# heating_pad_5v_to_3v.net
KiCad netlist of a schematic drawn in EAGLE
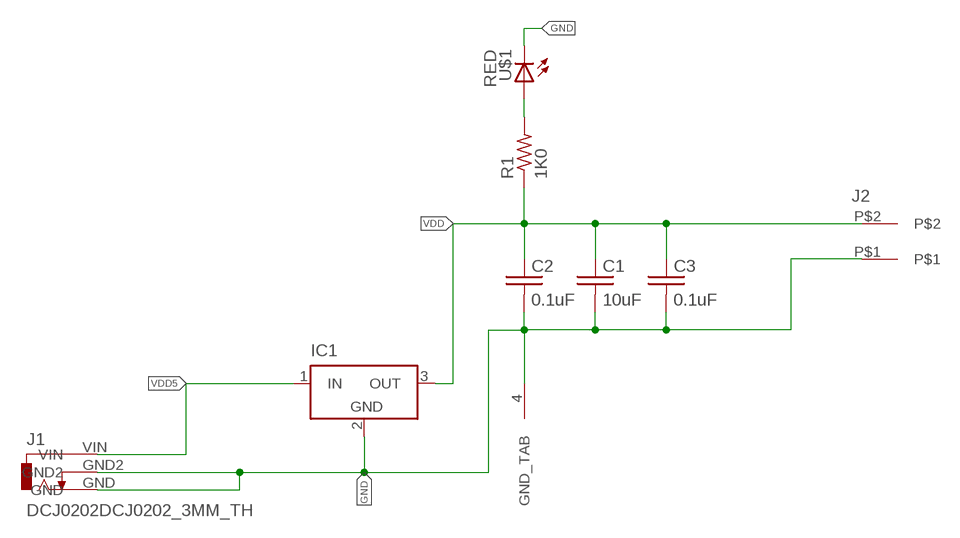
[diagram p0: schematic, sheet 1]

(export (version "E")
  (design (tool "Eeschema 10.0.6"))
  (components
    (comp (ref "C1")
      (value "10uF")
      (footprint "eagle-import:0402")
      (fields (field (name "PARTNO") "CL05A106MP8NUB8"))
      (libsource (lib "eagle-import") (part "C_0402_10UF"))
    )
    (comp (ref "C2")
      (value "0.1uF")
      (footprint "eagle-import:0402")
      (fields (field (name "PARTNO") "CL05F104ZO5NNNC"))
      (libsource (lib "eagle-import") (part "C_0402_0.1UF"))
    )
    (comp (ref "C3")
      (value "0.1uF")
      (footprint "eagle-import:0402")
      (fields (field (name "PARTNO") "CL05F104ZO5NNNC"))
      (libsource (lib "eagle-import") (part "C_0402_0.1UF"))
    )
    (comp (ref "IC1")
      (value "LT1129CST3")
      (footprint "eagle-import:SOT223")
      (libsource (lib "eagle-import") (part "LT1129CST3"))
    )
    (comp (ref "J1")
      (value "DCJ0202DCJ0202_3MM_TH")
      (footprint "eagle-import:DCJ0202_3MM_TH")
      (libsource (lib "eagle-import") (part "DCJ0202DCJ0202_3MM_TH"))
    )
    (comp (ref "J2")
      (value "2-pos")
      (footprint "eagle-import:2_3.81MM_PITCH")
      (fields (field (name "PARTNO") "691322310002"))
      (libsource (lib "eagle-import") (part "3.81MM_1_X_2_RT_ANGLE_PLUG_HEADER"))
    )
    (comp (ref "R1")
      (value "1K0")
      (footprint "eagle-import:0402")
      (fields (field (name "PARTNO") "CRG0402J1K0"))
      (libsource (lib "eagle-import") (part "R_0402_1K0"))
    )
    (comp (ref "U$1")
      (value "LED_0805_RED")
      (footprint "eagle-import:LED_0805_RED")
      (libsource (lib "eagle-import") (part "LED_0805_RED"))
    )
  )
  (nets
    (net (code "1") (name "GND") (class "Default")
      (node (ref "C1") (pin "P$2") (pinfunction "2_P$2") (pintype "passive"))
      (node (ref "C2") (pin "P$2") (pinfunction "2_P$2") (pintype "passive"))
      (node (ref "C3") (pin "P$2") (pinfunction "2_P$2") (pintype "passive"))
      (node (ref "IC1") (pin "2") (pinfunction "GND_2") (pintype "power_in"))
      (node (ref "IC1") (pin "4") (pinfunction "GND_TAB_4") (pintype "bidirectional"))
      (node (ref "J1") (pin "GND") (pinfunction "GND_GND") (pintype "power_in"))
      (node (ref "J1") (pin "GND2") (pinfunction "GND2_GND2") (pintype "power_in"))
      (node (ref "J2") (pin "P$1") (pinfunction "P$1_P$1") (pintype "bidirectional"))
      (node (ref "U$1") (pin "C") (pinfunction "C_C") (pintype "passive"))
    )
    (net (code "2") (name "Net-(R1-2)") (class "Default")
      (node (ref "R1") (pin "P$2") (pinfunction "2_P$2") (pintype "passive"))
      (node (ref "U$1") (pin "A") (pinfunction "A_A") (pintype "passive"))
    )
    (net (code "3") (name "VDD") (class "Default")
      (node (ref "C1") (pin "P$1") (pinfunction "1_P$1") (pintype "passive"))
      (node (ref "C2") (pin "P$1") (pinfunction "1_P$1") (pintype "passive"))
      (node (ref "C3") (pin "P$1") (pinfunction "1_P$1") (pintype "passive"))
      (node (ref "IC1") (pin "3") (pinfunction "OUT_3") (pintype "output"))
      (node (ref "J2") (pin "P$2") (pinfunction "P$2_P$2") (pintype "bidirectional"))
      (node (ref "R1") (pin "P$1") (pinfunction "1_P$1") (pintype "passive"))
    )
    (net (code "4") (name "VDD5") (class "Default")
      (node (ref "IC1") (pin "1") (pinfunction "IN_1") (pintype "input"))
      (node (ref "J1") (pin "VIN") (pinfunction "VIN_VIN") (pintype "power_in"))
    )
  )
)
